# pcb1a.net
KiCad netlist of a schematic drawn in EAGLE
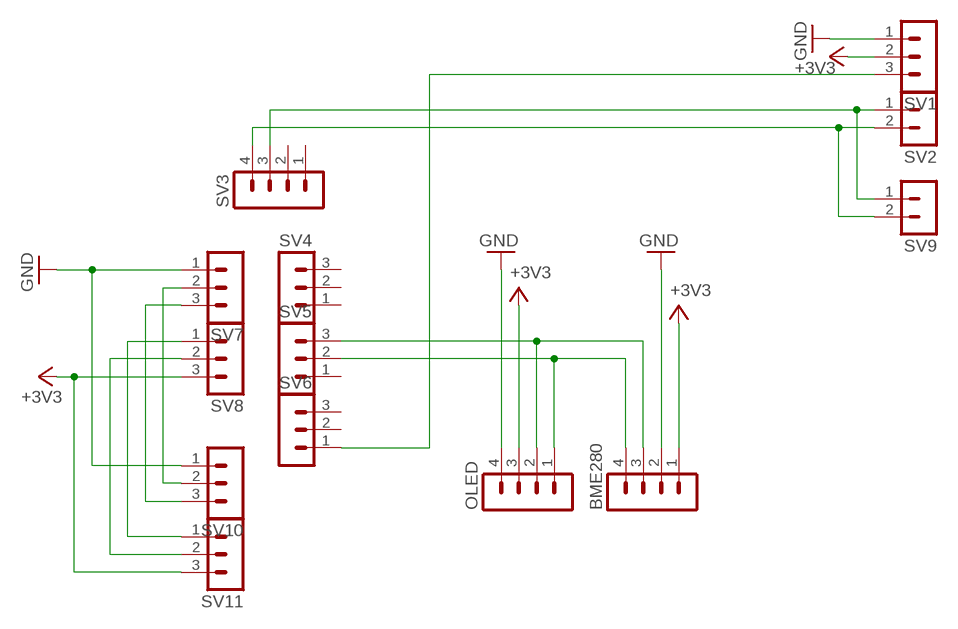
[diagram p0: schematic, sheet 1]

(export (version "E")
  (design (tool "Eeschema 10.0.6"))
  (components
    (comp (ref "BME280")
      (value "PINHEAD-MA04-1")
      (footprint "eagle-import:PINHEAD-MA04-1")
      (libsource (lib "eagle-import") (part "PINHEAD-MA04-1"))
    )
    (comp (ref "OLED")
      (value "PINHEAD-MA04-1")
      (footprint "eagle-import:PINHEAD-MA04-1")
      (libsource (lib "eagle-import") (part "PINHEAD-MA04-1"))
    )
    (comp (ref "SV1")
      (value "PINHEAD-MA03-1")
      (footprint "eagle-import:PINHEAD-MA03-1")
      (libsource (lib "eagle-import") (part "PINHEAD-MA03-1"))
    )
    (comp (ref "SV2")
      (value "PINHEAD-MA02-1")
      (footprint "eagle-import:PINHEAD-MA02-1")
      (libsource (lib "eagle-import") (part "PINHEAD-MA02-1"))
    )
    (comp (ref "SV3")
      (value "PINHEAD-MA04-1")
      (footprint "eagle-import:PINHEAD-MA04-1")
      (libsource (lib "eagle-import") (part "PINHEAD-MA04-1"))
    )
    (comp (ref "SV4")
      (value "PINHEAD-MA03-1")
      (footprint "eagle-import:PINHEAD-MA03-1")
      (libsource (lib "eagle-import") (part "PINHEAD-MA03-1"))
    )
    (comp (ref "SV5")
      (value "PINHEAD-MA03-1")
      (footprint "eagle-import:PINHEAD-MA03-1")
      (libsource (lib "eagle-import") (part "PINHEAD-MA03-1"))
    )
    (comp (ref "SV6")
      (value "PINHEAD-MA03-1")
      (footprint "eagle-import:PINHEAD-MA03-1")
      (libsource (lib "eagle-import") (part "PINHEAD-MA03-1"))
    )
    (comp (ref "SV7")
      (value "PINHEAD-MA03-1")
      (footprint "eagle-import:PINHEAD-MA03-1")
      (libsource (lib "eagle-import") (part "PINHEAD-MA03-1"))
    )
    (comp (ref "SV8")
      (value "PINHEAD-MA03-1")
      (footprint "eagle-import:PINHEAD-MA03-1")
      (libsource (lib "eagle-import") (part "PINHEAD-MA03-1"))
    )
    (comp (ref "SV9")
      (value "PINHEAD-MA02-1")
      (footprint "eagle-import:PINHEAD-MA02-1")
      (libsource (lib "eagle-import") (part "PINHEAD-MA02-1"))
    )
    (comp (ref "SV10")
      (value "PINHEAD-MA03-1")
      (footprint "eagle-import:PINHEAD-MA03-1")
      (libsource (lib "eagle-import") (part "PINHEAD-MA03-1"))
    )
    (comp (ref "SV11")
      (value "PINHEAD-MA03-1")
      (footprint "eagle-import:PINHEAD-MA03-1")
      (libsource (lib "eagle-import") (part "PINHEAD-MA03-1"))
    )
  )
  (nets
    (net (code "1") (name "+3V3") (class "Default")
      (node (ref "BME280") (pin "1") (pinfunction "1_1") (pintype "passive"))
      (node (ref "OLED") (pin "3") (pinfunction "3_3") (pintype "passive"))
      (node (ref "SV1") (pin "2") (pinfunction "2_2") (pintype "passive"))
      (node (ref "SV11") (pin "3") (pinfunction "3_3") (pintype "passive"))
      (node (ref "SV8") (pin "3") (pinfunction "3_3") (pintype "passive"))
    )
    (net (code "2") (name "GND") (class "Default")
      (node (ref "BME280") (pin "2") (pinfunction "2_2") (pintype "passive"))
      (node (ref "OLED") (pin "4") (pinfunction "4_4") (pintype "passive"))
      (node (ref "SV1") (pin "1") (pinfunction "1_1") (pintype "passive"))
      (node (ref "SV10") (pin "1") (pinfunction "1_1") (pintype "passive"))
      (node (ref "SV7") (pin "1") (pinfunction "1_1") (pintype "passive"))
    )
    (net (code "3") (name "Net-(BME280-Pad3)") (class "Default")
      (node (ref "BME280") (pin "3") (pinfunction "3_3") (pintype "passive"))
      (node (ref "OLED") (pin "2") (pinfunction "2_2") (pintype "passive"))
      (node (ref "SV5") (pin "3") (pinfunction "3_3") (pintype "passive"))
    )
    (net (code "4") (name "Net-(BME280-Pad4)") (class "Default")
      (node (ref "BME280") (pin "4") (pinfunction "4_4") (pintype "passive"))
      (node (ref "OLED") (pin "1") (pinfunction "1_1") (pintype "passive"))
      (node (ref "SV5") (pin "2") (pinfunction "2_2") (pintype "passive"))
    )
    (net (code "5") (name "Net-(SV1-Pad3)") (class "Default")
      (node (ref "SV1") (pin "3") (pinfunction "3_3") (pintype "passive"))
      (node (ref "SV6") (pin "1") (pinfunction "1_1") (pintype "passive"))
    )
    (net (code "6") (name "Net-(SV2-Pad1)") (class "Default")
      (node (ref "SV2") (pin "1") (pinfunction "1_1") (pintype "passive"))
      (node (ref "SV3") (pin "3") (pinfunction "3_3") (pintype "passive"))
      (node (ref "SV9") (pin "1") (pinfunction "1_1") (pintype "passive"))
    )
    (net (code "7") (name "Net-(SV2-Pad2)") (class "Default")
      (node (ref "SV2") (pin "2") (pinfunction "2_2") (pintype "passive"))
      (node (ref "SV3") (pin "4") (pinfunction "4_4") (pintype "passive"))
      (node (ref "SV9") (pin "2") (pinfunction "2_2") (pintype "passive"))
    )
    (net (code "8") (name "Net-(SV10-Pad2)") (class "Default")
      (node (ref "SV10") (pin "2") (pinfunction "2_2") (pintype "passive"))
      (node (ref "SV7") (pin "2") (pinfunction "2_2") (pintype "passive"))
    )
    (net (code "9") (name "Net-(SV10-Pad3)") (class "Default")
      (node (ref "SV10") (pin "3") (pinfunction "3_3") (pintype "passive"))
      (node (ref "SV7") (pin "3") (pinfunction "3_3") (pintype "passive"))
    )
    (net (code "10") (name "Net-(SV11-Pad1)") (class "Default")
      (node (ref "SV11") (pin "1") (pinfunction "1_1") (pintype "passive"))
      (node (ref "SV8") (pin "1") (pinfunction "1_1") (pintype "passive"))
    )
    (net (code "11") (name "Net-(SV11-Pad2)") (class "Default")
      (node (ref "SV11") (pin "2") (pinfunction "2_2") (pintype "passive"))
      (node (ref "SV8") (pin "2") (pinfunction "2_2") (pintype "passive"))
    )
    (net (code "12") (name "unconnected-(SV3-Pad1)") (class "Default")
      (node (ref "SV3") (pin "1") (pinfunction "1_1") (pintype "passive"))
    )
    (net (code "13") (name "unconnected-(SV3-Pad2)") (class "Default")
      (node (ref "SV3") (pin "2") (pinfunction "2_2") (pintype "passive"))
    )
    (net (code "14") (name "unconnected-(SV4-Pad1)") (class "Default")
      (node (ref "SV4") (pin "1") (pinfunction "1_1") (pintype "passive"))
    )
    (net (code "15") (name "unconnected-(SV4-Pad2)") (class "Default")
      (node (ref "SV4") (pin "2") (pinfunction "2_2") (pintype "passive"))
    )
    (net (code "16") (name "unconnected-(SV4-Pad3)") (class "Default")
      (node (ref "SV4") (pin "3") (pinfunction "3_3") (pintype "passive"))
    )
    (net (code "17") (name "unconnected-(SV5-Pad1)") (class "Default")
      (node (ref "SV5") (pin "1") (pinfunction "1_1") (pintype "passive"))
    )
    (net (code "18") (name "unconnected-(SV6-Pad2)") (class "Default")
      (node (ref "SV6") (pin "2") (pinfunction "2_2") (pintype "passive"))
    )
    (net (code "19") (name "unconnected-(SV6-Pad3)") (class "Default")
      (node (ref "SV6") (pin "3") (pinfunction "3_3") (pintype "passive"))
    )
  )
)
